# MAGI_sUSBASP.net
KiCad netlist of a schematic drawn in Altium Designer
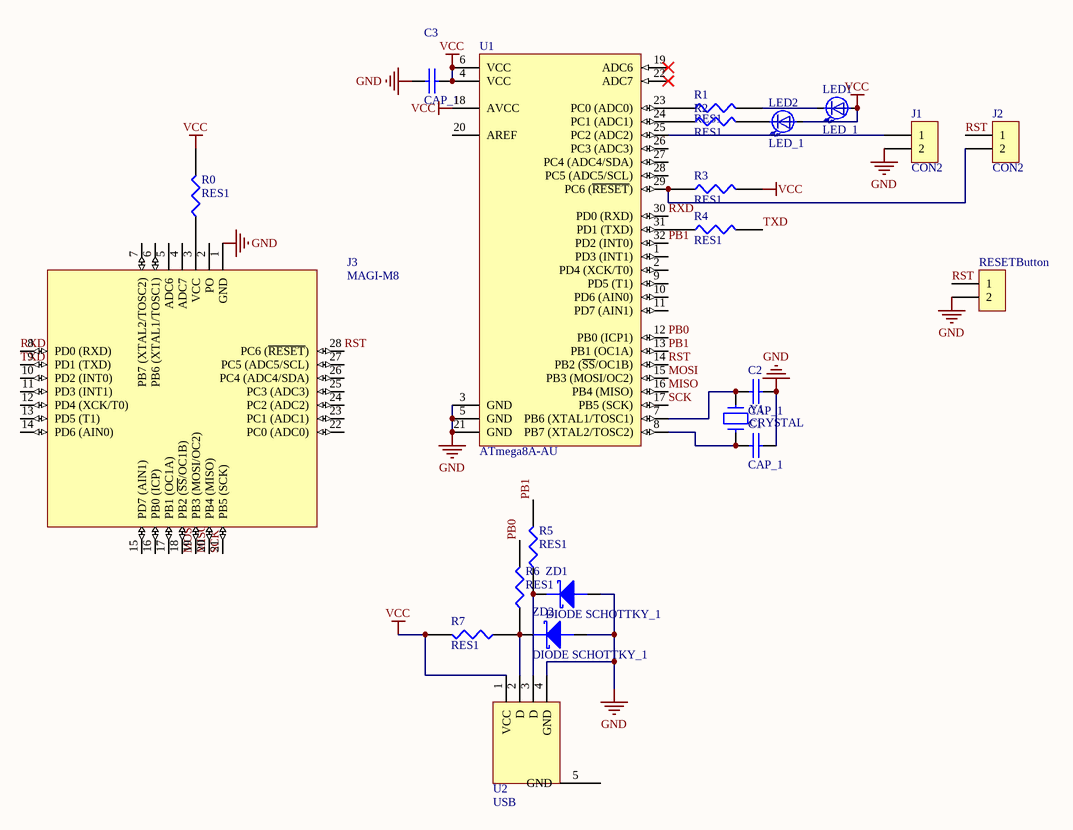
[diagram p0: MAGI'sUSBASP.SchDoc]

(export (version "E")
  (design (tool "Eeschema 10.0.6"))
  (components
    (comp (ref "C1")
      (value "CAP_1")
      (footprint "6-0805_M")
      (description "Capacitor")
      (libsource (lib "电容器") (part "CAP_1"))
    )
    (comp (ref "C2")
      (value "CAP_1")
      (footprint "6-0805_M")
      (description "Capacitor")
      (libsource (lib "电容器") (part "CAP_1"))
    )
    (comp (ref "C3")
      (value "CAP_1")
      (footprint "6-0805_M")
      (description "Capacitor")
      (libsource (lib "电容器") (part "CAP_1"))
    )
    (comp (ref "J1")
      (value "CON2")
      (footprint "6-0805_M")
      (description "Connector")
      (libsource (lib "CON系列") (part "CON2"))
    )
    (comp (ref "J2")
      (value "CON2")
      (footprint "6-0805_M")
      (description "Connector")
      (libsource (lib "CON系列") (part "CON2"))
    )
    (comp (ref "J3") (value "MAGI-M8") (footprint "MAGI-M8") (libsource (lib "MAGI-M8") (part "MAGI-M8")))
    (comp (ref "LED1") (value "LED_1") (footprint "6-0805_M") (libsource (lib "二极管") (part "LED_1")))
    (comp (ref "LED2") (value "LED_1") (footprint "6-0805_M") (libsource (lib "二极管") (part "LED_1")))
    (comp (ref "R0") (value "RES1") (footprint "6-0805_M") (libsource (lib "电阻器") (part "RES1")))
    (comp (ref "R1") (value "RES1") (footprint "6-0805_M") (libsource (lib "电阻器") (part "RES1")))
    (comp (ref "R2") (value "RES1") (footprint "6-0805_M") (libsource (lib "电阻器") (part "RES1")))
    (comp (ref "R3") (value "RES1") (footprint "6-0805_M") (libsource (lib "电阻器") (part "RES1")))
    (comp (ref "R4") (value "RES1") (footprint "6-0805_M") (libsource (lib "电阻器") (part "RES1")))
    (comp (ref "R5") (value "RES1") (footprint "6-0805_M") (libsource (lib "电阻器") (part "RES1")))
    (comp (ref "R6") (value "RES1") (footprint "6-0805_M") (libsource (lib "电阻器") (part "RES1")))
    (comp (ref "R7") (value "RES1") (footprint "6-0805_M") (libsource (lib "电阻器") (part "RES1")))
    (comp (ref "RESETButton")
      (value "~")
      (footprint "SKRELGE010")
      (description "Connector")
      (libsource (lib "CON系列") (part "CON2"))
    )
    (comp (ref "U1")
      (value "ATmega8A-AU")
      (footprint "32A_N")
      (fields (field (name "PUBLISHER") "Altium Limited"))
      (libsource (lib "Atmel Microcontroller 8-Bit megaAVR") (part "ATmega8A-AU"))
    )
    (comp (ref "U2") (value "USB") (footprint "MicroUSB") (libsource (lib "USB接口") (part "USB")))
    (comp (ref "Y1")
      (value "CRYSTAL")
      (footprint "4SMX")
      (description "Crystal")
      (libsource (lib "晶振") (part "CRYSTAL"))
    )
    (comp (ref "ZD1")
      (value "DIODE SCHOTTKY_1")
      (footprint "C1206")
      (description "Schottky Diode")
      (libsource (lib "二极管") (part "DIODE SCHOTTKY_1"))
    )
    (comp (ref "ZD2")
      (value "DIODE SCHOTTKY_1")
      (footprint "C1206")
      (description "Schottky Diode")
      (libsource (lib "二极管") (part "DIODE SCHOTTKY_1"))
    )
  )
  (nets
    (net (code "1") (name "/MISO") (class "Default")
      (node (ref "J3") (pin "20") (pinfunction "PB4_(MISO)_20") (pintype "bidirectional"))
      (node (ref "U1") (pin "16") (pinfunction "PB4_(MISO)_16") (pintype "bidirectional"))
    )
    (net (code "2") (name "/MOSI") (class "Default")
      (node (ref "J3") (pin "19") (pinfunction "PB3_(MOSI/OC2)_19") (pintype "bidirectional"))
      (node (ref "U1") (pin "15") (pinfunction "PB3_(MOSI/OC2)_15") (pintype "bidirectional"))
    )
    (net (code "3") (name "/PB0") (class "Default")
      (node (ref "R6") (pin "2") (pinfunction "2_2") (pintype "passive"))
      (node (ref "U1") (pin "12") (pinfunction "PB0_(ICP1)_12") (pintype "bidirectional"))
    )
    (net (code "4") (name "/PB1") (class "Default")
      (node (ref "R5") (pin "2") (pinfunction "2_2") (pintype "passive"))
      (node (ref "U1") (pin "13") (pinfunction "PB1_(OC1A)_13") (pintype "bidirectional"))
      (node (ref "U1") (pin "32") (pinfunction "PD2_(INT0)_32") (pintype "bidirectional"))
    )
    (net (code "5") (name "/RST") (class "Default")
      (node (ref "J2") (pin "1") (pinfunction "1_1") (pintype "passive"))
      (node (ref "J3") (pin "28") (pinfunction "PC6_(~{RESET})_28") (pintype "bidirectional"))
      (node (ref "RESETButton") (pin "1") (pinfunction "1_1") (pintype "passive"))
      (node (ref "U1") (pin "14") (pinfunction "PB2_(~{SS}/OC1B)_14") (pintype "bidirectional"))
    )
    (net (code "6") (name "/RXD") (class "Default")
      (node (ref "J3") (pin "8") (pinfunction "PD0_(RXD)_8") (pintype "bidirectional"))
      (node (ref "U1") (pin "30") (pinfunction "PD0_(RXD)_30") (pintype "bidirectional"))
    )
    (net (code "7") (name "/SCK") (class "Default")
      (node (ref "J3") (pin "21") (pinfunction "PB5_(SCK)_21") (pintype "bidirectional"))
      (node (ref "U1") (pin "17") (pinfunction "PB5_(SCK)_17") (pintype "bidirectional"))
    )
    (net (code "8") (name "/TXD") (class "Default")
      (node (ref "J3") (pin "9") (pinfunction "PD1_(TXD)_9") (pintype "bidirectional"))
      (node (ref "R4") (pin "2") (pinfunction "2_2") (pintype "passive"))
    )
    (net (code "9") (name "GND") (class "Default")
      (node (ref "C1") (pin "1") (pinfunction "1_1") (pintype "passive"))
      (node (ref "C2") (pin "1") (pinfunction "1_1") (pintype "passive"))
      (node (ref "C3") (pin "1") (pinfunction "1_1") (pintype "passive"))
      (node (ref "J1") (pin "2") (pinfunction "2_2") (pintype "passive"))
      (node (ref "J3") (pin "1") (pinfunction "GND_1") (pintype "power_in"))
      (node (ref "RESETButton") (pin "2") (pinfunction "2_2") (pintype "passive"))
      (node (ref "U1") (pin "21") (pinfunction "GND_21") (pintype "power_in"))
      (node (ref "U1") (pin "3") (pinfunction "GND_3") (pintype "power_in"))
      (node (ref "U1") (pin "5") (pinfunction "GND_5") (pintype "power_in"))
      (node (ref "U2") (pin "4") (pinfunction "GND_4") (pintype "passive"))
      (node (ref "ZD1") (pin "1") (pinfunction "A_1") (pintype "passive"))
      (node (ref "ZD2") (pin "1") (pinfunction "A_1") (pintype "passive"))
    )
    (net (code "10") (name "Net-(J3-VCC)") (class "Default")
      (node (ref "J3") (pin "3") (pinfunction "VCC_3") (pintype "power_in"))
      (node (ref "R0") (pin "1") (pinfunction "1_1") (pintype "passive"))
    )
    (net (code "11") (name "Net-(LED1-K)") (class "Default")
      (node (ref "LED1") (pin "2") (pinfunction "K_2") (pintype "passive"))
      (node (ref "R1") (pin "2") (pinfunction "2_2") (pintype "passive"))
    )
    (net (code "12") (name "Net-(LED2-K)") (class "Default")
      (node (ref "LED2") (pin "2") (pinfunction "K_2") (pintype "passive"))
      (node (ref "R2") (pin "2") (pinfunction "2_2") (pintype "passive"))
    )
    (net (code "13") (name "Net-(U1-PB6_(XTAL1{slash}TOSC1))") (class "Default")
      (node (ref "C2") (pin "2") (pinfunction "2_2") (pintype "passive"))
      (node (ref "U1") (pin "7") (pinfunction "PB6_(XTAL1/TOSC1)_7") (pintype "bidirectional"))
      (node (ref "Y1") (pin "1") (pinfunction "1_1") (pintype "passive"))
    )
    (net (code "14") (name "Net-(U1-PB7_(XTAL2{slash}TOSC2))") (class "Default")
      (node (ref "C1") (pin "2") (pinfunction "2_2") (pintype "passive"))
      (node (ref "U1") (pin "8") (pinfunction "PB7_(XTAL2/TOSC2)_8") (pintype "bidirectional"))
      (node (ref "Y1") (pin "2") (pinfunction "2_2") (pintype "passive"))
    )
    (net (code "15") (name "Net-(U1-PC0_(ADC0))") (class "Default")
      (node (ref "R1") (pin "1") (pinfunction "1_1") (pintype "passive"))
      (node (ref "U1") (pin "23") (pinfunction "PC0_(ADC0)_23") (pintype "bidirectional"))
    )
    (net (code "16") (name "Net-(U1-PC1_(ADC1))") (class "Default")
      (node (ref "R2") (pin "1") (pinfunction "1_1") (pintype "passive"))
      (node (ref "U1") (pin "24") (pinfunction "PC1_(ADC1)_24") (pintype "bidirectional"))
    )
    (net (code "17") (name "Net-(U1-PC2_(ADC2))") (class "Default")
      (node (ref "J1") (pin "1") (pinfunction "1_1") (pintype "passive"))
      (node (ref "U1") (pin "25") (pinfunction "PC2_(ADC2)_25") (pintype "bidirectional"))
    )
    (net (code "18") (name "Net-(U1-PC6_(~{RESET}))") (class "Default")
      (node (ref "J2") (pin "2") (pinfunction "2_2") (pintype "passive"))
      (node (ref "R3") (pin "1") (pinfunction "1_1") (pintype "passive"))
      (node (ref "U1") (pin "29") (pinfunction "PC6_(~{RESET})_29") (pintype "bidirectional"))
    )
    (net (code "19") (name "Net-(U1-PD1_(TXD))") (class "Default")
      (node (ref "R4") (pin "1") (pinfunction "1_1") (pintype "passive"))
      (node (ref "U1") (pin "31") (pinfunction "PD1_(TXD)_31") (pintype "bidirectional"))
    )
    (net (code "20") (name "Net-(ZD1-K)") (class "Default")
      (node (ref "R5") (pin "1") (pinfunction "1_1") (pintype "passive"))
      (node (ref "U2") (pin "3") (pinfunction "D_3") (pintype "passive"))
      (node (ref "ZD1") (pin "2") (pinfunction "K_2") (pintype "passive"))
    )
    (net (code "21") (name "Net-(ZD2-K)") (class "Default")
      (node (ref "R6") (pin "1") (pinfunction "1_1") (pintype "passive"))
      (node (ref "R7") (pin "1") (pinfunction "1_1") (pintype "passive"))
      (node (ref "U2") (pin "2") (pinfunction "D_2") (pintype "passive"))
      (node (ref "ZD2") (pin "2") (pinfunction "K_2") (pintype "passive"))
    )
    (net (code "22") (name "VCC") (class "Default")
      (node (ref "C3") (pin "2") (pinfunction "2_2") (pintype "passive"))
      (node (ref "LED1") (pin "1") (pinfunction "A_1") (pintype "passive"))
      (node (ref "LED2") (pin "1") (pinfunction "A_1") (pintype "passive"))
      (node (ref "R0") (pin "2") (pinfunction "2_2") (pintype "passive"))
      (node (ref "R3") (pin "2") (pinfunction "2_2") (pintype "passive"))
      (node (ref "R7") (pin "2") (pinfunction "2_2") (pintype "passive"))
      (node (ref "U1") (pin "18") (pinfunction "AVCC_18") (pintype "power_in"))
      (node (ref "U1") (pin "4") (pinfunction "VCC_4") (pintype "power_in"))
      (node (ref "U1") (pin "6") (pinfunction "VCC_6") (pintype "power_in"))
      (node (ref "U2") (pin "1") (pinfunction "VCC_1") (pintype "passive"))
    )
    (net (code "23") (name "unconnected-(J3-ADC6-Pad5)") (class "Default")
      (node (ref "J3") (pin "5") (pinfunction "ADC6_5") (pintype "passive"))
    )
    (net (code "24") (name "unconnected-(J3-ADC7-Pad4)") (class "Default")
      (node (ref "J3") (pin "4") (pinfunction "ADC7_4") (pintype "passive"))
    )
    (net (code "25") (name "unconnected-(J3-PB0_(ICP)-Pad16)") (class "Default")
      (node (ref "J3") (pin "16") (pinfunction "PB0_(ICP)_16") (pintype "bidirectional"))
    )
    (net (code "26") (name "unconnected-(J3-PB1_(OC1A)-Pad17)") (class "Default")
      (node (ref "J3") (pin "17") (pinfunction "PB1_(OC1A)_17") (pintype "bidirectional"))
    )
    (net (code "27") (name "unconnected-(J3-PB2_(~{SS}{slash}OC1B)-Pad18)") (class "Default")
      (node (ref "J3") (pin "18") (pinfunction "PB2_(~{SS}/OC1B)_18") (pintype "bidirectional"))
    )
    (net (code "28") (name "unconnected-(J3-PB6_(XTAL1{slash}TOSC1)-Pad6)") (class "Default")
      (node (ref "J3") (pin "6") (pinfunction "PB6_(XTAL1/TOSC1)_6") (pintype "bidirectional"))
    )
    (net (code "29") (name "unconnected-(J3-PB7_(XTAL2{slash}TOSC2)-Pad7)") (class "Default")
      (node (ref "J3") (pin "7") (pinfunction "PB7_(XTAL2/TOSC2)_7") (pintype "bidirectional"))
    )
    (net (code "30") (name "unconnected-(J3-PC0_(ADC0)-Pad22)") (class "Default")
      (node (ref "J3") (pin "22") (pinfunction "PC0_(ADC0)_22") (pintype "bidirectional"))
    )
    (net (code "31") (name "unconnected-(J3-PC1_(ADC1)-Pad23)") (class "Default")
      (node (ref "J3") (pin "23") (pinfunction "PC1_(ADC1)_23") (pintype "bidirectional"))
    )
    (net (code "32") (name "unconnected-(J3-PC2_(ADC2)-Pad24)") (class "Default")
      (node (ref "J3") (pin "24") (pinfunction "PC2_(ADC2)_24") (pintype "bidirectional"))
    )
    (net (code "33") (name "unconnected-(J3-PC3_(ADC3)-Pad25)") (class "Default")
      (node (ref "J3") (pin "25") (pinfunction "PC3_(ADC3)_25") (pintype "bidirectional"))
    )
    (net (code "34") (name "unconnected-(J3-PC4_(ADC4{slash}SDA)-Pad26)") (class "Default")
      (node (ref "J3") (pin "26") (pinfunction "PC4_(ADC4/SDA)_26") (pintype "bidirectional"))
    )
    (net (code "35") (name "unconnected-(J3-PC5_(ADC5{slash}SCL)-Pad27)") (class "Default")
      (node (ref "J3") (pin "27") (pinfunction "PC5_(ADC5/SCL)_27") (pintype "bidirectional"))
    )
    (net (code "36") (name "unconnected-(J3-PD2_(INT0)-Pad10)") (class "Default")
      (node (ref "J3") (pin "10") (pinfunction "PD2_(INT0)_10") (pintype "bidirectional"))
    )
    (net (code "37") (name "unconnected-(J3-PD3_(INT1)-Pad11)") (class "Default")
      (node (ref "J3") (pin "11") (pinfunction "PD3_(INT1)_11") (pintype "bidirectional"))
    )
    (net (code "38") (name "unconnected-(J3-PD4_(XCK{slash}T0)-Pad12)") (class "Default")
      (node (ref "J3") (pin "12") (pinfunction "PD4_(XCK/T0)_12") (pintype "bidirectional"))
    )
    (net (code "39") (name "unconnected-(J3-PD5_(T1)-Pad13)") (class "Default")
      (node (ref "J3") (pin "13") (pinfunction "PD5_(T1)_13") (pintype "bidirectional"))
    )
    (net (code "40") (name "unconnected-(J3-PD6_(AIN0)-Pad14)") (class "Default")
      (node (ref "J3") (pin "14") (pinfunction "PD6_(AIN0)_14") (pintype "bidirectional"))
    )
    (net (code "41") (name "unconnected-(J3-PD7_(AIN1)-Pad15)") (class "Default")
      (node (ref "J3") (pin "15") (pinfunction "PD7_(AIN1)_15") (pintype "bidirectional"))
    )
    (net (code "42") (name "unconnected-(J3-PO-Pad2)") (class "Default")
      (node (ref "J3") (pin "2") (pinfunction "PO_2") (pintype "power_in"))
    )
    (net (code "43") (name "unconnected-(U1-ADC6-Pad19)") (class "Default")
      (node (ref "U1") (pin "19") (pinfunction "ADC6_19") (pintype "input+no_connect"))
    )
    (net (code "44") (name "unconnected-(U1-ADC7-Pad22)") (class "Default")
      (node (ref "U1") (pin "22") (pinfunction "ADC7_22") (pintype "input+no_connect"))
    )
    (net (code "45") (name "unconnected-(U1-AREF-Pad20)") (class "Default")
      (node (ref "U1") (pin "20") (pinfunction "AREF_20") (pintype "power_in"))
    )
    (net (code "46") (name "unconnected-(U1-PC3_(ADC3)-Pad26)") (class "Default")
      (node (ref "U1") (pin "26") (pinfunction "PC3_(ADC3)_26") (pintype "bidirectional"))
    )
    (net (code "47") (name "unconnected-(U1-PC4_(ADC4{slash}SDA)-Pad27)") (class "Default")
      (node (ref "U1") (pin "27") (pinfunction "PC4_(ADC4/SDA)_27") (pintype "bidirectional"))
    )
    (net (code "48") (name "unconnected-(U1-PC5_(ADC5{slash}SCL)-Pad28)") (class "Default")
      (node (ref "U1") (pin "28") (pinfunction "PC5_(ADC5/SCL)_28") (pintype "bidirectional"))
    )
    (net (code "49") (name "unconnected-(U1-PD3_(INT1)-Pad1)") (class "Default")
      (node (ref "U1") (pin "1") (pinfunction "PD3_(INT1)_1") (pintype "bidirectional"))
    )
    (net (code "50") (name "unconnected-(U1-PD4_(XCK{slash}T0)-Pad2)") (class "Default")
      (node (ref "U1") (pin "2") (pinfunction "PD4_(XCK/T0)_2") (pintype "bidirectional"))
    )
    (net (code "51") (name "unconnected-(U1-PD5_(T1)-Pad9)") (class "Default")
      (node (ref "U1") (pin "9") (pinfunction "PD5_(T1)_9") (pintype "bidirectional"))
    )
    (net (code "52") (name "unconnected-(U1-PD6_(AIN0)-Pad10)") (class "Default")
      (node (ref "U1") (pin "10") (pinfunction "PD6_(AIN0)_10") (pintype "bidirectional"))
    )
    (net (code "53") (name "unconnected-(U1-PD7_(AIN1)-Pad11)") (class "Default")
      (node (ref "U1") (pin "11") (pinfunction "PD7_(AIN1)_11") (pintype "bidirectional"))
    )
    (net (code "54") (name "unconnected-(U2-GND-Pad5)") (class "Default")
      (node (ref "U2") (pin "5") (pinfunction "GND_5") (pintype "passive"))
    )
  )
)
